# pot-boardDesp2.net
KiCad netlist of a schematic drawn in EAGLE
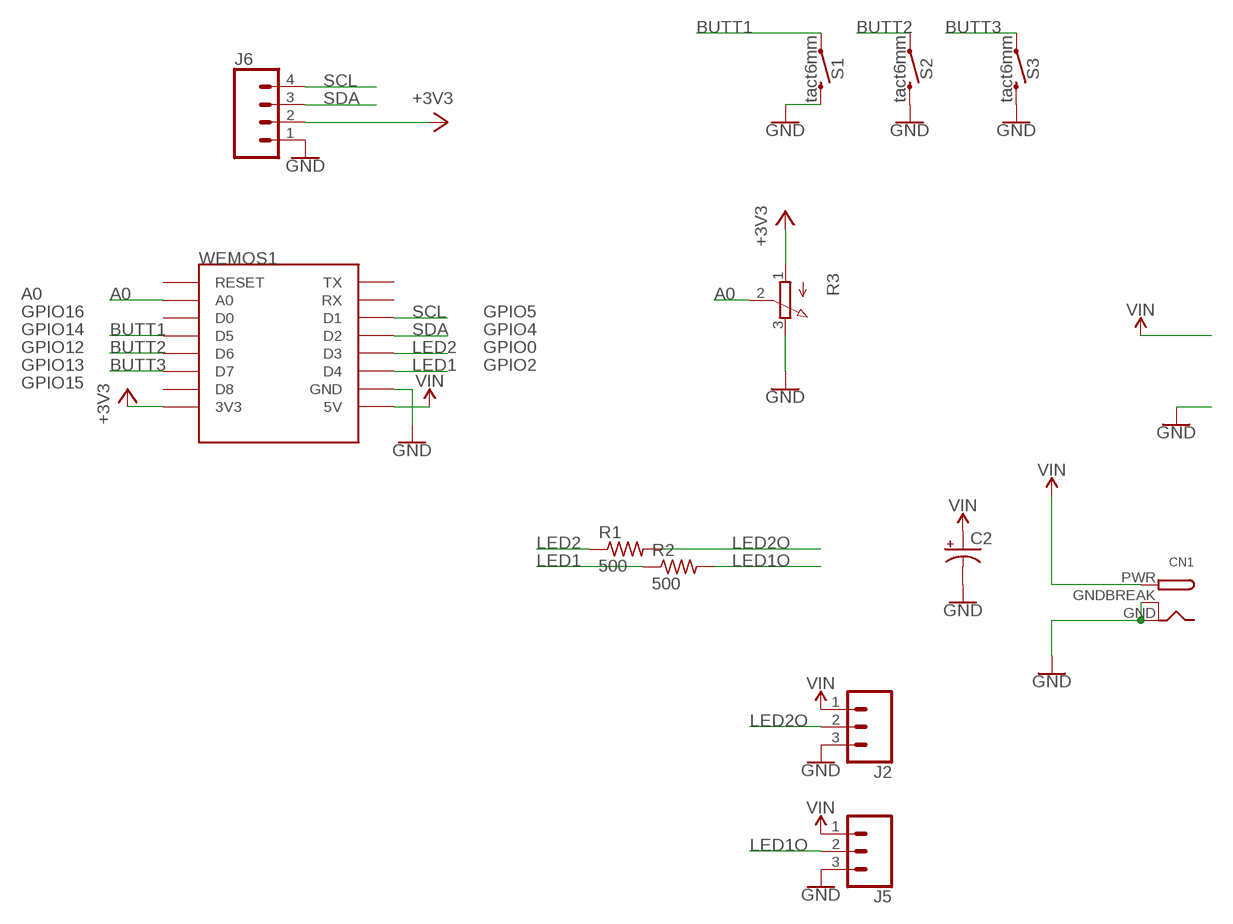
[diagram p0: schematic, sheet 1]

(export (version "E")
  (design (tool "Eeschema 10.0.6"))
  (components
    (comp (ref "C2")
      (value "CPOL-USE3.5-8")
      (footprint "eagle-import:E3,5-8")
      (libsource (lib "eagle-import") (part "CPOL-USE3.5-8"))
    )
    (comp (ref "CN1")
      (value "DCBARRELPTH")
      (footprint "eagle-import:DCJACK_2MM_PTH")
      (libsource (lib "eagle-import") (part "DCBARRELPTH"))
    )
    (comp (ref "J2")
      (value "CONN_03")
      (footprint "eagle-import:1X03")
      (libsource (lib "eagle-import") (part "CONN_03"))
    )
    (comp (ref "J5")
      (value "CONN_03")
      (footprint "eagle-import:1X03")
      (libsource (lib "eagle-import") (part "CONN_03"))
    )
    (comp (ref "J6")
      (value "CONN_04")
      (footprint "eagle-import:1X04")
      (libsource (lib "eagle-import") (part "CONN_04"))
    )
    (comp (ref "R1")
      (value "500")
      (footprint "eagle-import:R0805")
      (libsource (lib "eagle-import") (part "R-US_R0805"))
    )
    (comp (ref "R2")
      (value "500")
      (footprint "eagle-import:R0805")
      (libsource (lib "eagle-import") (part "R-US_R0805"))
    )
    (comp (ref "R3")
      (value "3RP/1610N")
      (footprint "eagle-import:3RP_1610N")
      (libsource (lib "eagle-import") (part "3RP/1610N"))
    )
    (comp (ref "S1")
      (value "tact6mm")
      (footprint "eagle-import:TACTILE_SWITCH_PTH_6.0MM")
      (libsource (lib "eagle-import") (part "MOMENTARY-SWITCH-SPST-PTH-6.0MM"))
    )
    (comp (ref "S2")
      (value "tact6mm")
      (footprint "eagle-import:TACTILE_SWITCH_PTH_6.0MM")
      (libsource (lib "eagle-import") (part "MOMENTARY-SWITCH-SPST-PTH-6.0MM"))
    )
    (comp (ref "S3")
      (value "tact6mm")
      (footprint "eagle-import:TACTILE_SWITCH_PTH_6.0MM")
      (libsource (lib "eagle-import") (part "MOMENTARY-SWITCH-SPST-PTH-6.0MM"))
    )
    (comp (ref "WEMOS1")
      (value "WEMOS-D1-MINI")
      (footprint "eagle-import:WEMOS-D1-MINI")
      (libsource (lib "eagle-import") (part "WEMOS-D1-MINI"))
    )
  )
  (nets
    (net (code "1") (name "+3V3") (class "Default")
      (node (ref "J6") (pin "2") (pinfunction "2_2") (pintype "passive"))
      (node (ref "R3") (pin "1") (pinfunction "A_1") (pintype "passive"))
      (node (ref "WEMOS1") (pin "3V3") (pinfunction "3V3_3V3") (pintype "bidirectional"))
    )
    (net (code "2") (name "/A0") (class "Default")
      (node (ref "R3") (pin "2") (pinfunction "S_2") (pintype "passive"))
      (node (ref "WEMOS1") (pin "A0") (pinfunction "A0_A0") (pintype "bidirectional"))
    )
    (net (code "3") (name "/BUTT1") (class "Default")
      (node (ref "S1") (pin "1") (pinfunction "1_1") (pintype "passive"))
      (node (ref "WEMOS1") (pin "D5") (pinfunction "D5_D5") (pintype "bidirectional"))
    )
    (net (code "4") (name "/BUTT2") (class "Default")
      (node (ref "S2") (pin "1") (pinfunction "1_1") (pintype "passive"))
      (node (ref "WEMOS1") (pin "D6") (pinfunction "D6_D6") (pintype "bidirectional"))
    )
    (net (code "5") (name "/BUTT3") (class "Default")
      (node (ref "S3") (pin "1") (pinfunction "1_1") (pintype "passive"))
      (node (ref "WEMOS1") (pin "D7") (pinfunction "D7_D7") (pintype "bidirectional"))
    )
    (net (code "6") (name "/LED1") (class "Default")
      (node (ref "R2") (pin "1") (pinfunction "1_1") (pintype "passive"))
      (node (ref "WEMOS1") (pin "D4") (pinfunction "D4_D4") (pintype "bidirectional"))
    )
    (net (code "7") (name "/LED1O") (class "Default")
      (node (ref "J5") (pin "2") (pinfunction "2_2") (pintype "passive"))
      (node (ref "R2") (pin "2") (pinfunction "2_2") (pintype "passive"))
    )
    (net (code "8") (name "/LED2") (class "Default")
      (node (ref "R1") (pin "1") (pinfunction "1_1") (pintype "passive"))
      (node (ref "WEMOS1") (pin "D3") (pinfunction "D3_D3") (pintype "bidirectional"))
    )
    (net (code "9") (name "/LED2O") (class "Default")
      (node (ref "J2") (pin "2") (pinfunction "2_2") (pintype "passive"))
      (node (ref "R1") (pin "2") (pinfunction "2_2") (pintype "passive"))
    )
    (net (code "10") (name "/SCL") (class "Default")
      (node (ref "J6") (pin "4") (pinfunction "4_4") (pintype "passive"))
      (node (ref "WEMOS1") (pin "D1") (pinfunction "D1_D1") (pintype "bidirectional"))
    )
    (net (code "11") (name "/SDA") (class "Default")
      (node (ref "J6") (pin "3") (pinfunction "3_3") (pintype "passive"))
      (node (ref "WEMOS1") (pin "D2") (pinfunction "D2_D2") (pintype "bidirectional"))
    )
    (net (code "12") (name "GND") (class "Default")
      (node (ref "C2") (pin "-") (pinfunction "-_-") (pintype "passive"))
      (node (ref "CN1") (pin "GND") (pinfunction "GND_GND") (pintype "power_in"))
      (node (ref "CN1") (pin "GNDBREAK") (pinfunction "GNDBREAK_GNDBREAK") (pintype "power_in"))
      (node (ref "J2") (pin "3") (pinfunction "3_3") (pintype "passive"))
      (node (ref "J5") (pin "3") (pinfunction "3_3") (pintype "passive"))
      (node (ref "J6") (pin "1") (pinfunction "1_1") (pintype "passive"))
      (node (ref "R3") (pin "3") (pinfunction "E_3") (pintype "passive"))
      (node (ref "S1") (pin "3") (pinfunction "2_3") (pintype "passive"))
      (node (ref "S2") (pin "3") (pinfunction "2_3") (pintype "passive"))
      (node (ref "S3") (pin "3") (pinfunction "2_3") (pintype "passive"))
      (node (ref "WEMOS1") (pin "GND") (pinfunction "GND_GND") (pintype "bidirectional"))
    )
    (net (code "13") (name "VIN") (class "Default")
      (node (ref "C2") (pin "+") (pinfunction "+_+") (pintype "passive"))
      (node (ref "CN1") (pin "PWR") (pinfunction "PWR_PWR") (pintype "power_in"))
      (node (ref "J2") (pin "1") (pinfunction "1_1") (pintype "passive"))
      (node (ref "J5") (pin "1") (pinfunction "1_1") (pintype "passive"))
      (node (ref "WEMOS1") (pin "5V") (pinfunction "5V_5V") (pintype "bidirectional"))
    )
    (net (code "14") (name "unconnected-(WEMOS1-PadD0)") (class "Default")
      (node (ref "WEMOS1") (pin "D0") (pinfunction "D0_D0") (pintype "bidirectional"))
    )
    (net (code "15") (name "unconnected-(WEMOS1-PadD8)") (class "Default")
      (node (ref "WEMOS1") (pin "D8") (pinfunction "D8_D8") (pintype "bidirectional"))
    )
    (net (code "16") (name "unconnected-(WEMOS1-PadRESET)") (class "Default")
      (node (ref "WEMOS1") (pin "RESET") (pinfunction "RESET_RESET") (pintype "bidirectional"))
    )
    (net (code "17") (name "unconnected-(WEMOS1-PadRX)") (class "Default")
      (node (ref "WEMOS1") (pin "RX") (pinfunction "RX_RX") (pintype "bidirectional"))
    )
    (net (code "18") (name "unconnected-(WEMOS1-PadTX)") (class "Default")
      (node (ref "WEMOS1") (pin "TX") (pinfunction "TX_TX") (pintype "bidirectional"))
    )
  )
)
